# CS_JFETOnSemiSOT23_v1.net
KiCad netlist of a schematic drawn in Altium Designer
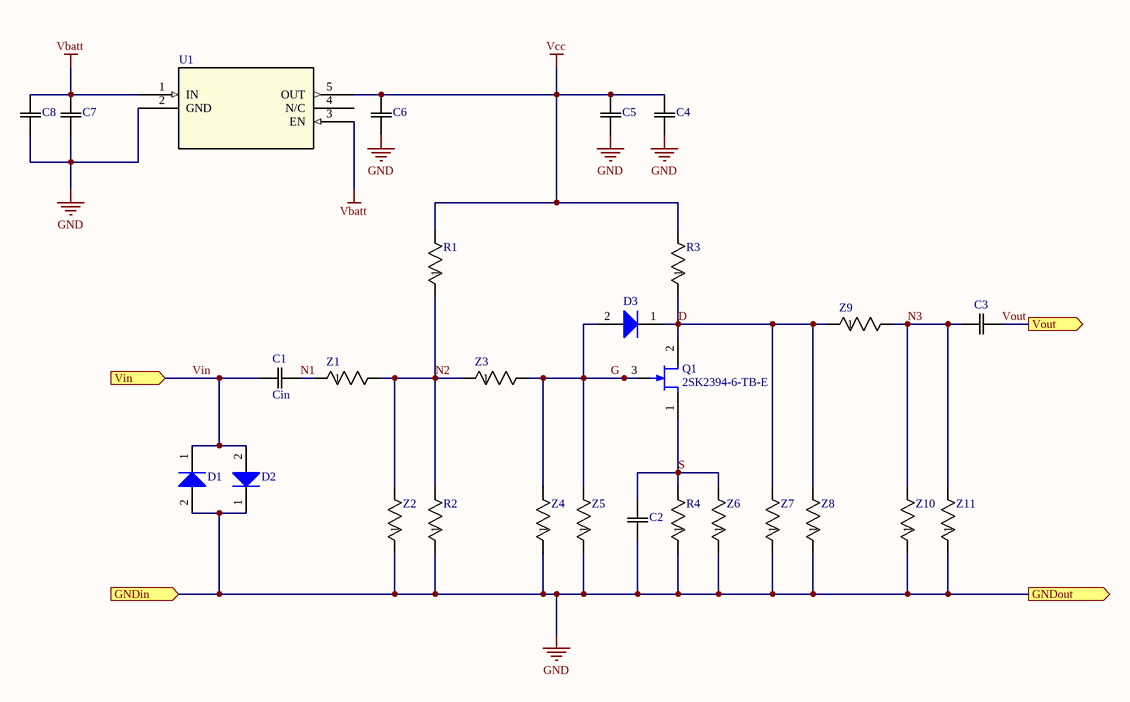
[diagram p0: CS_JFETOnSemiSOT23_v1.SchDoc]

(export (version "E")
  (design (tool "Eeschema 10.0.6"))
  (components
    (comp (ref "C1")
      (value "Cin")
      (footprint "C0201")
      (description "No Description Available")
      (fields
        (field (name "MANUFACTURER_PART_NUMBER") "C0201C270J3GACTU")
        (field (name "COPYRIGHT") "Copyright (C) 2018 Accelerated Designs. All rights reserved")
      )
      (libsource (lib "0201Capacitor_Yageo") (part "C0201C270J3GACTU"))
    )
    (comp (ref "C2")
      (value "~")
      (footprint "C0201")
      (description "No Description Available")
      (fields
        (field (name "MANUFACTURER_PART_NUMBER") "C0201C270J3GACTU")
        (field (name "COPYRIGHT") "Copyright (C) 2018 Accelerated Designs. All rights reserved")
      )
      (libsource (lib "0201Capacitor_Yageo") (part "C0201C270J3GACTU"))
    )
    (comp (ref "C3")
      (value "~")
      (footprint "C0201")
      (description "No Description Available")
      (fields
        (field (name "MANUFACTURER_PART_NUMBER") "C0201C270J3GACTU")
        (field (name "COPYRIGHT") "Copyright (C) 2018 Accelerated Designs. All rights reserved")
      )
      (libsource (lib "0201Capacitor_Yageo") (part "C0201C270J3GACTU"))
    )
    (comp (ref "C4")
      (value "~")
      (footprint "CAP_CBR_0201")
      (description "No Description Available")
      (fields
        (field (name "MANUFACTURER_PART_NUMBER") "CBR02C399C3GAC")
        (field (name "COPYRIGHT") "Copyright (C) 2018 Accelerated Designs. All rights reserved")
      )
      (libsource (lib "0201Capacitor_KEMET") (part "CBR02C399C3GAC"))
    )
    (comp (ref "C5")
      (value "~")
      (footprint "CAP_CBR_0201")
      (description "No Description Available")
      (fields
        (field (name "MANUFACTURER_PART_NUMBER") "CBR02C399C3GAC")
        (field (name "COPYRIGHT") "Copyright (C) 2018 Accelerated Designs. All rights reserved")
      )
      (libsource (lib "0201Capacitor_KEMET") (part "CBR02C399C3GAC"))
    )
    (comp (ref "C6")
      (value "~")
      (footprint "YAG_CC0402")
      (description "No Description Available")
      (fields
        (field (name "MANUFACTURER_PART_NUMBER") "CC0402KRX7R9BB103")
        (field (name "COPYRIGHT") "Copyright (C) 2018 Accelerated Designs. All rights reserved")
      )
      (libsource (lib "0402Capacitor_Yageo") (part "CC0402KRX7R9BB10"))
    )
    (comp (ref "C7")
      (value "~")
      (footprint "YAG_CC0402")
      (description "No Description Available")
      (fields
        (field (name "MANUFACTURER_PART_NUMBER") "CC0402KRX7R9BB103")
        (field (name "COPYRIGHT") "Copyright (C) 2018 Accelerated Designs. All rights reserved")
      )
      (libsource (lib "0402Capacitor_Yageo") (part "CC0402KRX7R9BB10"))
    )
    (comp (ref "C8")
      (value "~")
      (footprint "YAG_CC0402")
      (description "No Description Available")
      (fields
        (field (name "MANUFACTURER_PART_NUMBER") "CC0402KRX7R9BB103")
        (field (name "COPYRIGHT") "Copyright (C) 2018 Accelerated Designs. All rights reserved")
      )
      (libsource (lib "0402Capacitor_Yageo") (part "CC0402KRX7R9BB10"))
    )
    (comp (ref "D1")
      (value "~")
      (footprint "INF-SOD323_V")
      (description "Single Silicon Schottky Diode, 110 mA IF Max, SOD32, Green")
      (fields (field (name "MANUFACTURER") "Infineon") (field (name "PARTNUMBER") "BAT15-03W"))
      (libsource (lib "Infineon_RFSchottkyDiode_SOD323") (part "BAT15-03W"))
    )
    (comp (ref "D2")
      (value "~")
      (footprint "INF-SOD323_V")
      (description "Single Silicon Schottky Diode, 110 mA IF Max, SOD32, Green")
      (fields (field (name "MANUFACTURER") "Infineon") (field (name "PARTNUMBER") "BAT15-03W"))
      (libsource (lib "Infineon_RFSchottkyDiode_SOD323") (part "BAT15-03W"))
    )
    (comp (ref "D3")
      (value "~")
      (footprint "INF-SOD323_V")
      (description "Single Silicon Schottky Diode, 110 mA IF Max, SOD32, Green")
      (fields (field (name "MANUFACTURER") "Infineon") (field (name "PARTNUMBER") "BAT15-03W"))
      (libsource (lib "Infineon_RFSchottkyDiode_SOD323") (part "BAT15-03W"))
    )
    (comp (ref "Q1")
      (value "2SK2394-6-TB-E")
      (footprint "ONSC-CP-3-318AN_A_V")
      (description "N-Channel JFET, 15 V, 10 to 20 mA, 38 mS, 3-Pin CP, Pb-Free, Tape and Reel")
      (fields (field (name "MANUFACTURER") "On Semiconductor"))
      (libsource (lib "ON Semi JFETs") (part "2SK2394-6-TB-E"))
    )
    (comp (ref "R1")
      (value "~")
      (footprint "RES_RC0201_P6XP3")
      (description "No Description Available")
      (fields
        (field (name "MANUFACTURER_PART_NUMBER") "RC0201FR-0718KL")
        (field (name "COPYRIGHT") "Copyright (C) 2018 Accelerated Designs. All rights reserved")
      )
      (libsource (lib "0201Resistor_Yageo") (part "RC0201FR-0718KL"))
    )
    (comp (ref "R2")
      (value "~")
      (footprint "RES_RC0201_P6XP3")
      (description "No Description Available")
      (fields
        (field (name "MANUFACTURER_PART_NUMBER") "RC0201FR-0718KL")
        (field (name "COPYRIGHT") "Copyright (C) 2018 Accelerated Designs. All rights reserved")
      )
      (libsource (lib "0201Resistor_Yageo") (part "RC0201FR-0718KL"))
    )
    (comp (ref "R3")
      (value "~")
      (footprint "RES_RC0201_P6XP3")
      (description "No Description Available")
      (fields
        (field (name "MANUFACTURER_PART_NUMBER") "RC0201FR-0718KL")
        (field (name "COPYRIGHT") "Copyright (C) 2018 Accelerated Designs. All rights reserved")
      )
      (libsource (lib "0201Resistor_Yageo") (part "RC0201FR-0718KL"))
    )
    (comp (ref "R4")
      (value "~")
      (footprint "RES_RC0201_P6XP3")
      (description "No Description Available")
      (fields
        (field (name "MANUFACTURER_PART_NUMBER") "RC0201FR-0718KL")
        (field (name "COPYRIGHT") "Copyright (C) 2018 Accelerated Designs. All rights reserved")
      )
      (libsource (lib "0201Resistor_Yageo") (part "RC0201FR-0718KL"))
    )
    (comp (ref "U1")
      (value "~")
      (footprint "DBV5")
      (description "No Description Available")
      (fields
        (field (name "MANUFACTURER_PART_NUMBER") "LP5907MFX-3.3/NOPB")
        (field (name "COPYRIGHT") "Copyright (C) 2018 Accelerated Designs. All rights reserved")
      )
      (libsource (lib "TI_LDO_3V3_SOT325") (part "LP5907MFX-3.3/NO"))
    )
    (comp (ref "Z1")
      (value "~")
      (footprint "RES_RC0201_P6XP3")
      (description "No Description Available")
      (fields
        (field (name "MANUFACTURER_PART_NUMBER") "RC0201FR-0718KL")
        (field (name "COPYRIGHT") "Copyright (C) 2018 Accelerated Designs. All rights reserved")
      )
      (libsource (lib "0201Resistor_Yageo") (part "RC0201FR-0718KL"))
    )
    (comp (ref "Z2")
      (value "~")
      (footprint "RES_RC0201_P6XP3")
      (description "No Description Available")
      (fields
        (field (name "MANUFACTURER_PART_NUMBER") "RC0201FR-0718KL")
        (field (name "COPYRIGHT") "Copyright (C) 2018 Accelerated Designs. All rights reserved")
      )
      (libsource (lib "0201Resistor_Yageo") (part "RC0201FR-0718KL"))
    )
    (comp (ref "Z3")
      (value "~")
      (footprint "RES_RC0201_P6XP3")
      (description "No Description Available")
      (fields
        (field (name "MANUFACTURER_PART_NUMBER") "RC0201FR-0718KL")
        (field (name "COPYRIGHT") "Copyright (C) 2018 Accelerated Designs. All rights reserved")
      )
      (libsource (lib "0201Resistor_Yageo") (part "RC0201FR-0718KL"))
    )
    (comp (ref "Z4")
      (value "~")
      (footprint "RES_RC0201_P6XP3")
      (description "No Description Available")
      (fields
        (field (name "MANUFACTURER_PART_NUMBER") "RC0201FR-0718KL")
        (field (name "COPYRIGHT") "Copyright (C) 2018 Accelerated Designs. All rights reserved")
      )
      (libsource (lib "0201Resistor_Yageo") (part "RC0201FR-0718KL"))
    )
    (comp (ref "Z5")
      (value "~")
      (footprint "RES_RC0201_P6XP3")
      (description "No Description Available")
      (fields
        (field (name "MANUFACTURER_PART_NUMBER") "RC0201FR-0718KL")
        (field (name "COPYRIGHT") "Copyright (C) 2018 Accelerated Designs. All rights reserved")
      )
      (libsource (lib "0201Resistor_Yageo") (part "RC0201FR-0718KL"))
    )
    (comp (ref "Z6")
      (value "~")
      (footprint "RES_RC0201_P6XP3")
      (description "No Description Available")
      (fields
        (field (name "MANUFACTURER_PART_NUMBER") "RC0201FR-0718KL")
        (field (name "COPYRIGHT") "Copyright (C) 2018 Accelerated Designs. All rights reserved")
      )
      (libsource (lib "0201Resistor_Yageo") (part "RC0201FR-0718KL"))
    )
    (comp (ref "Z7")
      (value "~")
      (footprint "RES_RC0201_P6XP3")
      (description "No Description Available")
      (fields
        (field (name "MANUFACTURER_PART_NUMBER") "RC0201FR-0718KL")
        (field (name "COPYRIGHT") "Copyright (C) 2018 Accelerated Designs. All rights reserved")
      )
      (libsource (lib "0201Resistor_Yageo") (part "RC0201FR-0718KL"))
    )
    (comp (ref "Z8")
      (value "~")
      (footprint "RES_RC0201_P6XP3")
      (description "No Description Available")
      (fields
        (field (name "MANUFACTURER_PART_NUMBER") "RC0201FR-0718KL")
        (field (name "COPYRIGHT") "Copyright (C) 2018 Accelerated Designs. All rights reserved")
      )
      (libsource (lib "0201Resistor_Yageo") (part "RC0201FR-0718KL"))
    )
    (comp (ref "Z9")
      (value "~")
      (footprint "RES_RC0201_P6XP3")
      (description "No Description Available")
      (fields
        (field (name "MANUFACTURER_PART_NUMBER") "RC0201FR-0718KL")
        (field (name "COPYRIGHT") "Copyright (C) 2018 Accelerated Designs. All rights reserved")
      )
      (libsource (lib "0201Resistor_Yageo") (part "RC0201FR-0718KL"))
    )
    (comp (ref "Z10")
      (value "~")
      (footprint "RES_RC0201_P6XP3")
      (description "No Description Available")
      (fields
        (field (name "MANUFACTURER_PART_NUMBER") "RC0201FR-0718KL")
        (field (name "COPYRIGHT") "Copyright (C) 2018 Accelerated Designs. All rights reserved")
      )
      (libsource (lib "0201Resistor_Yageo") (part "RC0201FR-0718KL"))
    )
    (comp (ref "Z11")
      (value "~")
      (footprint "RES_RC0201_P6XP3")
      (description "No Description Available")
      (fields
        (field (name "MANUFACTURER_PART_NUMBER") "RC0201FR-0718KL")
        (field (name "COPYRIGHT") "Copyright (C) 2018 Accelerated Designs. All rights reserved")
      )
      (libsource (lib "0201Resistor_Yageo") (part "RC0201FR-0718KL"))
    )
  )
  (nets
    (net (code "1") (name "/D") (class "Default")
      (node (ref "D3") (pin "1") (pinfunction "K_1") (pintype "passive"))
      (node (ref "Q1") (pin "2") (pinfunction "D_2") (pintype "passive"))
      (node (ref "R3") (pin "1") (pinfunction "1_1") (pintype "passive"))
      (node (ref "Z7") (pin "2") (pinfunction "2_2") (pintype "passive"))
      (node (ref "Z8") (pin "2") (pinfunction "2_2") (pintype "passive"))
      (node (ref "Z9") (pin "1") (pinfunction "1_1") (pintype "passive"))
    )
    (net (code "2") (name "/G") (class "Default")
      (node (ref "D3") (pin "2") (pinfunction "A_2") (pintype "passive"))
      (node (ref "Q1") (pin "3") (pinfunction "G_3") (pintype "passive"))
      (node (ref "Z3") (pin "2") (pinfunction "2_2") (pintype "passive"))
      (node (ref "Z4") (pin "2") (pinfunction "2_2") (pintype "passive"))
      (node (ref "Z5") (pin "2") (pinfunction "2_2") (pintype "passive"))
    )
    (net (code "3") (name "/N1") (class "Default")
      (node (ref "C1") (pin "2") (pinfunction "2_2") (pintype "passive"))
      (node (ref "Z1") (pin "1") (pinfunction "1_1") (pintype "passive"))
    )
    (net (code "4") (name "/N2") (class "Default")
      (node (ref "R1") (pin "1") (pinfunction "1_1") (pintype "passive"))
      (node (ref "R2") (pin "2") (pinfunction "2_2") (pintype "passive"))
      (node (ref "Z1") (pin "2") (pinfunction "2_2") (pintype "passive"))
      (node (ref "Z2") (pin "2") (pinfunction "2_2") (pintype "passive"))
      (node (ref "Z3") (pin "1") (pinfunction "1_1") (pintype "passive"))
    )
    (net (code "5") (name "/N3") (class "Default")
      (node (ref "C3") (pin "1") (pinfunction "1_1") (pintype "passive"))
      (node (ref "Z10") (pin "2") (pinfunction "2_2") (pintype "passive"))
      (node (ref "Z11") (pin "2") (pinfunction "2_2") (pintype "passive"))
      (node (ref "Z9") (pin "2") (pinfunction "2_2") (pintype "passive"))
    )
    (net (code "6") (name "/S") (class "Default")
      (node (ref "C2") (pin "2") (pinfunction "2_2") (pintype "passive"))
      (node (ref "Q1") (pin "1") (pinfunction "S_1") (pintype "passive"))
      (node (ref "R4") (pin "2") (pinfunction "2_2") (pintype "passive"))
      (node (ref "Z6") (pin "2") (pinfunction "2_2") (pintype "passive"))
    )
    (net (code "7") (name "/Vin") (class "Default")
      (node (ref "C1") (pin "1") (pinfunction "1_1") (pintype "passive"))
      (node (ref "D1") (pin "1") (pinfunction "K_1") (pintype "passive"))
      (node (ref "D2") (pin "2") (pinfunction "A_2") (pintype "passive"))
    )
    (net (code "8") (name "/Vout") (class "Default")
      (node (ref "C3") (pin "2") (pinfunction "2_2") (pintype "passive"))
    )
    (net (code "9") (name "GND") (class "Default")
      (node (ref "C2") (pin "1") (pinfunction "1_1") (pintype "passive"))
      (node (ref "C4") (pin "1") (pinfunction "1_1") (pintype "passive"))
      (node (ref "C5") (pin "1") (pinfunction "1_1") (pintype "passive"))
      (node (ref "C6") (pin "1") (pinfunction "1_1") (pintype "passive"))
      (node (ref "C7") (pin "1") (pinfunction "1_1") (pintype "passive"))
      (node (ref "C8") (pin "1") (pinfunction "1_1") (pintype "passive"))
      (node (ref "D1") (pin "2") (pinfunction "A_2") (pintype "passive"))
      (node (ref "D2") (pin "1") (pinfunction "K_1") (pintype "passive"))
      (node (ref "R2") (pin "1") (pinfunction "1_1") (pintype "passive"))
      (node (ref "R4") (pin "1") (pinfunction "1_1") (pintype "passive"))
      (node (ref "U1") (pin "2") (pinfunction "GND_2") (pintype "power_in"))
      (node (ref "Z10") (pin "1") (pinfunction "1_1") (pintype "passive"))
      (node (ref "Z11") (pin "1") (pinfunction "1_1") (pintype "passive"))
      (node (ref "Z2") (pin "1") (pinfunction "1_1") (pintype "passive"))
      (node (ref "Z4") (pin "1") (pinfunction "1_1") (pintype "passive"))
      (node (ref "Z5") (pin "1") (pinfunction "1_1") (pintype "passive"))
      (node (ref "Z6") (pin "1") (pinfunction "1_1") (pintype "passive"))
      (node (ref "Z7") (pin "1") (pinfunction "1_1") (pintype "passive"))
      (node (ref "Z8") (pin "1") (pinfunction "1_1") (pintype "passive"))
    )
    (net (code "10") (name "Vbatt") (class "Default")
      (node (ref "C7") (pin "2") (pinfunction "2_2") (pintype "passive"))
      (node (ref "C8") (pin "2") (pinfunction "2_2") (pintype "passive"))
      (node (ref "U1") (pin "1") (pinfunction "IN_1") (pintype "input"))
      (node (ref "U1") (pin "3") (pinfunction "EN_3") (pintype "input"))
    )
    (net (code "11") (name "Vcc") (class "Default")
      (node (ref "C4") (pin "2") (pinfunction "2_2") (pintype "passive"))
      (node (ref "C5") (pin "2") (pinfunction "2_2") (pintype "passive"))
      (node (ref "C6") (pin "2") (pinfunction "2_2") (pintype "passive"))
      (node (ref "R1") (pin "2") (pinfunction "2_2") (pintype "passive"))
      (node (ref "R3") (pin "2") (pinfunction "2_2") (pintype "passive"))
      (node (ref "U1") (pin "5") (pinfunction "OUT_5") (pintype "output"))
    )
    (net (code "12") (name "unconnected-(U1-N{slash}C-Pad4)") (class "Default")
      (node (ref "U1") (pin "4") (pinfunction "N/C_4") (pintype "passive"))
    )
  )
)
